# DS12885.net
KiCad netlist of a schematic drawn in Altium Designer
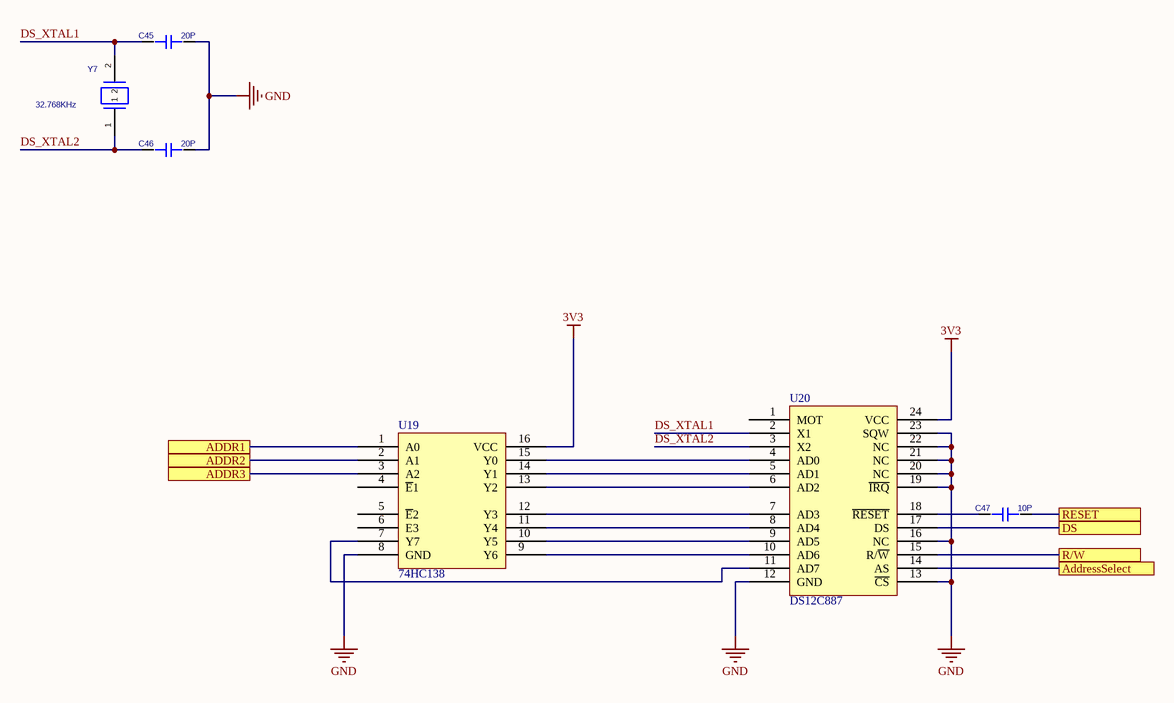
[diagram p0: DS12885.SchDoc]

(export (version "E")
  (design (tool "Eeschema 10.0.6"))
  (components
    (comp (ref "C45")
      (value "20P")
      (footprint "CAP_0603_FIRE")
      (fields (field (name "Comment") "CAP_20P_0603_FIRE"))
      (libsource (lib "MINI-V3") (part "CAP_20P_0603_FIRE"))
    )
    (comp (ref "C46")
      (value "20P")
      (footprint "CAP_0603_FIRE")
      (fields (field (name "Comment") "CAP_20P_0603_FIRE"))
      (libsource (lib "MINI-V3") (part "CAP_20P_0603_FIRE"))
    )
    (comp (ref "C47")
      (value "10P")
      (footprint "RES_0603_FIRE")
      (description "0603")
      (fields (field (name "TOLERANCE") "+-5%") (field (name "Comment") "CAP_10P_0603_FIRE"))
      (libsource (lib "MINI-V3") (part "CAP_10P_0603_FIRE"))
    )
    (comp (ref "U19") (value "74HC138") (footprint "74HC138") (libsource (lib "Inte_Car") (part "74HC138")))
    (comp (ref "U20") (value "DS12C887") (footprint "DS12885") (libsource (lib "Inte_Car") (part "DS12C887")))
    (comp (ref "Y7")
      (value "32.768KHz")
      (footprint "3215")
      (description "CRYSTAL")
      (fields (field (name "Comment") "XTAL_32.768KHZ_3215"))
      (libsource (lib "MINI-V3") (part "XTAL_32.768KHZ_3215"))
    )
  )
  (nets
    (net (code "1") (name "/ADDR1") (class "Default")
      (node (ref "U19") (pin "1") (pinfunction "A0_1") (pintype "passive"))
    )
    (net (code "2") (name "/ADDR2") (class "Default")
      (node (ref "U19") (pin "2") (pinfunction "A1_2") (pintype "passive"))
    )
    (net (code "3") (name "/ADDR3") (class "Default")
      (node (ref "U19") (pin "3") (pinfunction "A2_3") (pintype "passive"))
    )
    (net (code "4") (name "/AddressSelect") (class "Default")
      (node (ref "U20") (pin "14") (pinfunction "AS_14") (pintype "passive"))
    )
    (net (code "5") (name "/DS") (class "Default")
      (node (ref "U20") (pin "17") (pinfunction "DS_17") (pintype "passive"))
    )
    (net (code "6") (name "/DS_XTAL1") (class "Default")
      (node (ref "C45") (pin "1") (pinfunction "1_1") (pintype "passive"))
      (node (ref "U20") (pin "2") (pinfunction "X1_2") (pintype "passive"))
      (node (ref "Y7") (pin "2") (pinfunction "2_2") (pintype "passive"))
    )
    (net (code "7") (name "/DS_XTAL2") (class "Default")
      (node (ref "C46") (pin "1") (pinfunction "1_1") (pintype "passive"))
      (node (ref "U20") (pin "3") (pinfunction "X2_3") (pintype "passive"))
      (node (ref "Y7") (pin "1") (pinfunction "1_1") (pintype "passive"))
    )
    (net (code "8") (name "/RESET") (class "Default")
      (node (ref "C47") (pin "2") (pinfunction "2_2") (pintype "passive"))
    )
    (net (code "9") (name "/R{slash}W") (class "Default")
      (node (ref "U20") (pin "15") (pinfunction "R/~{W}_15") (pintype "passive"))
    )
    (net (code "10") (name "3V3") (class "Default")
      (node (ref "U19") (pin "16") (pinfunction "VCC_16") (pintype "passive"))
      (node (ref "U20") (pin "24") (pinfunction "VCC_24") (pintype "passive"))
    )
    (net (code "11") (name "GND") (class "Default")
      (node (ref "C45") (pin "2") (pinfunction "2_2") (pintype "passive"))
      (node (ref "C46") (pin "2") (pinfunction "2_2") (pintype "passive"))
      (node (ref "U19") (pin "8") (pinfunction "GND_8") (pintype "passive"))
      (node (ref "U20") (pin "12") (pinfunction "GND_12") (pintype "passive"))
      (node (ref "U20") (pin "13") (pinfunction "~{CS}_13") (pintype "passive"))
      (node (ref "U20") (pin "16") (pinfunction "NC_16") (pintype "passive"))
      (node (ref "U20") (pin "19") (pinfunction "~{IRQ}_19") (pintype "passive"))
      (node (ref "U20") (pin "20") (pinfunction "NC_20") (pintype "passive"))
      (node (ref "U20") (pin "21") (pinfunction "NC_21") (pintype "passive"))
      (node (ref "U20") (pin "22") (pinfunction "NC_22") (pintype "passive"))
      (node (ref "U20") (pin "23") (pinfunction "SQW_23") (pintype "passive"))
    )
    (net (code "12") (name "Net-(U19-Y0)") (class "Default")
      (node (ref "U19") (pin "15") (pinfunction "Y0_15") (pintype "passive"))
      (node (ref "U20") (pin "4") (pinfunction "AD0_4") (pintype "passive"))
    )
    (net (code "13") (name "Net-(U19-Y1)") (class "Default")
      (node (ref "U19") (pin "14") (pinfunction "Y1_14") (pintype "passive"))
      (node (ref "U20") (pin "5") (pinfunction "AD1_5") (pintype "passive"))
    )
    (net (code "14") (name "Net-(U19-Y2)") (class "Default")
      (node (ref "U19") (pin "13") (pinfunction "Y2_13") (pintype "passive"))
      (node (ref "U20") (pin "6") (pinfunction "AD2_6") (pintype "passive"))
    )
    (net (code "15") (name "Net-(U19-Y3)") (class "Default")
      (node (ref "U19") (pin "12") (pinfunction "Y3_12") (pintype "passive"))
      (node (ref "U20") (pin "7") (pinfunction "AD3_7") (pintype "passive"))
    )
    (net (code "16") (name "Net-(U19-Y4)") (class "Default")
      (node (ref "U19") (pin "11") (pinfunction "Y4_11") (pintype "passive"))
      (node (ref "U20") (pin "8") (pinfunction "AD4_8") (pintype "passive"))
    )
    (net (code "17") (name "Net-(U19-Y5)") (class "Default")
      (node (ref "U19") (pin "10") (pinfunction "Y5_10") (pintype "passive"))
      (node (ref "U20") (pin "9") (pinfunction "AD5_9") (pintype "passive"))
    )
    (net (code "18") (name "Net-(U19-Y6)") (class "Default")
      (node (ref "U19") (pin "9") (pinfunction "Y6_9") (pintype "passive"))
      (node (ref "U20") (pin "10") (pinfunction "AD6_10") (pintype "passive"))
    )
    (net (code "19") (name "Net-(U19-Y7)") (class "Default")
      (node (ref "U19") (pin "7") (pinfunction "Y7_7") (pintype "passive"))
      (node (ref "U20") (pin "11") (pinfunction "AD7_11") (pintype "passive"))
    )
    (net (code "20") (name "Net-(U20-~{RESET})") (class "Default")
      (node (ref "C47") (pin "1") (pinfunction "1_1") (pintype "passive"))
      (node (ref "U20") (pin "18") (pinfunction "~{RESET}_18") (pintype "passive"))
    )
    (net (code "21") (name "unconnected-(U19-E3-Pad6)") (class "Default")
      (node (ref "U19") (pin "6") (pinfunction "E3_6") (pintype "passive"))
    )
    (net (code "22") (name "unconnected-(U19-~{E}1-Pad4)") (class "Default")
      (node (ref "U19") (pin "4") (pinfunction "~{E}1_4") (pintype "passive"))
    )
    (net (code "23") (name "unconnected-(U19-~{E}2-Pad5)") (class "Default")
      (node (ref "U19") (pin "5") (pinfunction "~{E}2_5") (pintype "passive"))
    )
    (net (code "24") (name "unconnected-(U20-MOT-Pad1)") (class "Default")
      (node (ref "U20") (pin "1") (pinfunction "MOT_1") (pintype "passive"))
    )
  )
)
